# ZHSD-ZYNQ-PWR.net
KiCad netlist of a schematic drawn in Altium Designer
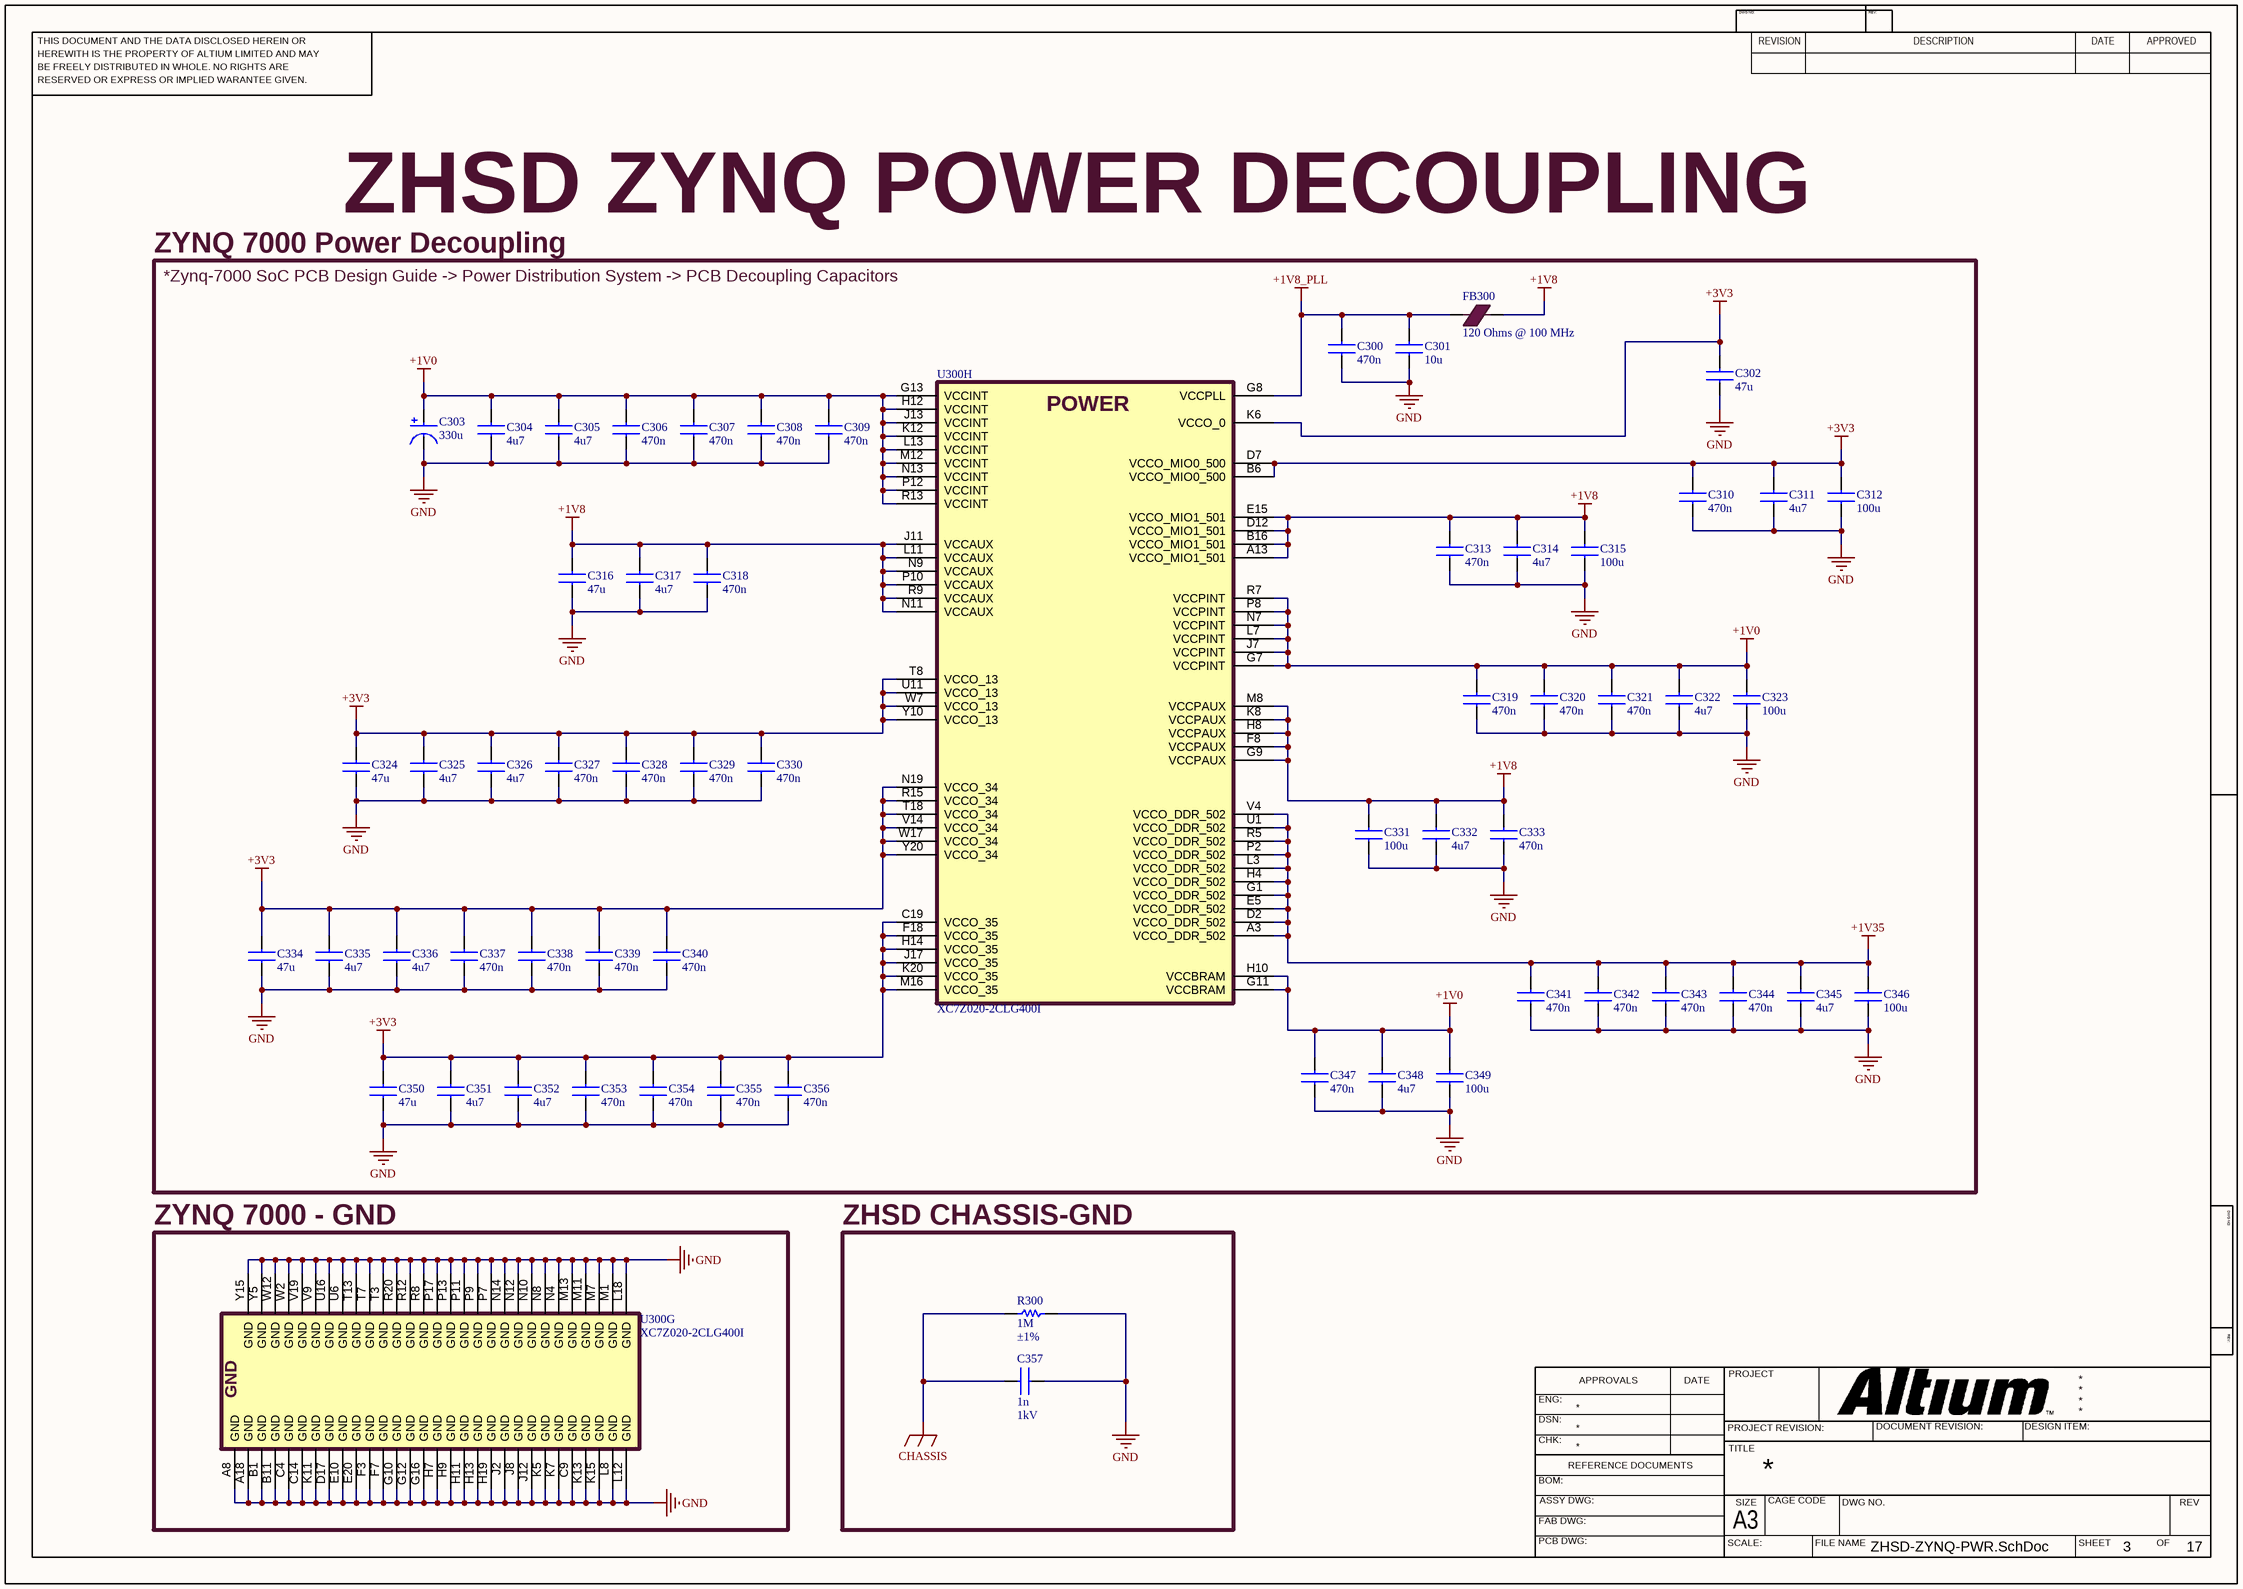
[diagram p0: ZHSD-ZYNQ-PWR.SchDoc]

(export (version "E")
  (design (tool "Eeschema 10.0.6"))
  (components
    (comp (ref "C300")
      (value "470n")
      (footprint "0402CAPC1005X06N")
      (description "CAP CER 0.47UF 6.3V X5R 0402(1005) ±10%")
      (fields (field (name "MANUFACTURER") "Murata Electronics") (field (name "MPN") "GRM155R60J474KE19D"))
      (libsource (lib "UK_Library") (part "GRM155R60J474KE19D"))
    )
    (comp (ref "C301")
      (value "10u")
      (footprint "0603CAPC1608X09N")
      (description "CAP CER 10UF 4V X5R 0603 (1608) ±20%")
      (fields (field (name "MANUFACTURER") "Murata Electronics") (field (name "MPN") "GRM188R60G106ME47D"))
      (libsource (lib "UK_Library") (part "GRM188R60G106ME47D"))
    )
    (comp (ref "C302")
      (value "47u")
      (footprint "1210CAPC3225X27N")
      (description "CAP CER 47UF 6.3V X7R 1210 1210 (3225) ±20%")
      (fields (field (name "MANUFACTURER") "Murata Electronics") (field (name "MPN") "GRM32ER70J476ME20L"))
      (libsource (lib "UK_Library") (part "GRM32ER70J476ME20L"))
    )
    (comp (ref "C303")
      (value "330u")
      (footprint "T525D337M006ATE025")
      (description "CAP TANT POLY 330UF 6.3V 2917 (7343) ±20%")
      (fields (field (name "MANUFACTURER") "KEMET") (field (name "MPN") "T525D337M006ATE025"))
      (libsource (lib "UK_Library") (part "T525D337M006ATE025"))
    )
    (comp (ref "C304")
      (value "4u7")
      (footprint "0603CAPC1608X09N")
      (description "CAP CER 4.7UF 10V X5R 0603 (1608) ±10%")
      (fields
        (field (name "MANUFACTURER") "Samsung Electro-Mechanics")
        (field (name "MPN") "CL10A475KP8NNNC")
      )
      (libsource (lib "UK_Library") (part "CL10A475KP8NNNC"))
    )
    (comp (ref "C305")
      (value "4u7")
      (footprint "0603CAPC1608X09N")
      (description "CAP CER 4.7UF 10V X5R 0603 (1608) ±10%")
      (fields
        (field (name "MANUFACTURER") "Samsung Electro-Mechanics")
        (field (name "MPN") "CL10A475KP8NNNC")
      )
      (libsource (lib "UK_Library") (part "CL10A475KP8NNNC"))
    )
    (comp (ref "C306")
      (value "470n")
      (footprint "0402CAPC1005X06N")
      (description "CAP CER 0.47UF 6.3V X5R 0402(1005) ±10%")
      (fields (field (name "MANUFACTURER") "Murata Electronics") (field (name "MPN") "GRM155R60J474KE19D"))
      (libsource (lib "UK_Library") (part "GRM155R60J474KE19D"))
    )
    (comp (ref "C307")
      (value "470n")
      (footprint "0402CAPC1005X06N")
      (description "CAP CER 0.47UF 6.3V X5R 0402(1005) ±10%")
      (fields (field (name "MANUFACTURER") "Murata Electronics") (field (name "MPN") "GRM155R60J474KE19D"))
      (libsource (lib "UK_Library") (part "GRM155R60J474KE19D"))
    )
    (comp (ref "C308")
      (value "470n")
      (footprint "0402CAPC1005X06N")
      (description "CAP CER 0.47UF 6.3V X5R 0402(1005) ±10%")
      (fields (field (name "MANUFACTURER") "Murata Electronics") (field (name "MPN") "GRM155R60J474KE19D"))
      (libsource (lib "UK_Library") (part "GRM155R60J474KE19D"))
    )
    (comp (ref "C309")
      (value "470n")
      (footprint "0402CAPC1005X06N")
      (description "CAP CER 0.47UF 6.3V X5R 0402(1005) ±10%")
      (fields (field (name "MANUFACTURER") "Murata Electronics") (field (name "MPN") "GRM155R60J474KE19D"))
      (libsource (lib "UK_Library") (part "GRM155R60J474KE19D"))
    )
    (comp (ref "C310")
      (value "470n")
      (footprint "0402CAPC1005X06N")
      (description "CAP CER 0.47UF 6.3V X5R 0402(1005) ±10%")
      (fields (field (name "MANUFACTURER") "Murata Electronics") (field (name "MPN") "GRM155R60J474KE19D"))
      (libsource (lib "UK_Library") (part "GRM155R60J474KE19D"))
    )
    (comp (ref "C311")
      (value "4u7")
      (footprint "0603CAPC1608X09N")
      (description "CAP CER 4.7UF 10V X5R 0603 (1608) ±10%")
      (fields
        (field (name "MANUFACTURER") "Samsung Electro-Mechanics")
        (field (name "MPN") "CL10A475KP8NNNC")
      )
      (libsource (lib "UK_Library") (part "CL10A475KP8NNNC"))
    )
    (comp (ref "C312")
      (value "100u")
      (footprint "1210CAPC3225X27N")
      (description "CAP CER 100UF 4V X7U 1210 (3225) ±20%")
      (fields (field (name "MANUFACTURER") "Murata Electronics") (field (name "MPN") "GRM32EE70G107ME19L"))
      (libsource (lib "UK_Library") (part "GRM32EE70G107ME19L"))
    )
    (comp (ref "C313")
      (value "470n")
      (footprint "0402CAPC1005X06N")
      (description "CAP CER 0.47UF 6.3V X5R 0402(1005) ±10%")
      (fields (field (name "MANUFACTURER") "Murata Electronics") (field (name "MPN") "GRM155R60J474KE19D"))
      (libsource (lib "UK_Library") (part "GRM155R60J474KE19D"))
    )
    (comp (ref "C314")
      (value "4u7")
      (footprint "0603CAPC1608X09N")
      (description "CAP CER 4.7UF 10V X5R 0603 (1608) ±10%")
      (fields
        (field (name "MANUFACTURER") "Samsung Electro-Mechanics")
        (field (name "MPN") "CL10A475KP8NNNC")
      )
      (libsource (lib "UK_Library") (part "CL10A475KP8NNNC"))
    )
    (comp (ref "C315")
      (value "100u")
      (footprint "1210CAPC3225X27N")
      (description "CAP CER 100UF 4V X7U 1210 (3225) ±20%")
      (fields (field (name "MANUFACTURER") "Murata Electronics") (field (name "MPN") "GRM32EE70G107ME19L"))
      (libsource (lib "UK_Library") (part "GRM32EE70G107ME19L"))
    )
    (comp (ref "C316")
      (value "47u")
      (footprint "1210CAPC3225X27N")
      (description "CAP CER 47UF 6.3V X7R 1210 1210 (3225) ±20%")
      (fields (field (name "MANUFACTURER") "Murata Electronics") (field (name "MPN") "GRM32ER70J476ME20L"))
      (libsource (lib "UK_Library") (part "GRM32ER70J476ME20L"))
    )
    (comp (ref "C317")
      (value "4u7")
      (footprint "0603CAPC1608X09N")
      (description "CAP CER 4.7UF 10V X5R 0603 (1608) ±10%")
      (fields
        (field (name "MANUFACTURER") "Samsung Electro-Mechanics")
        (field (name "MPN") "CL10A475KP8NNNC")
      )
      (libsource (lib "UK_Library") (part "CL10A475KP8NNNC"))
    )
    (comp (ref "C318")
      (value "470n")
      (footprint "0402CAPC1005X06N")
      (description "CAP CER 0.47UF 6.3V X5R 0402(1005) ±10%")
      (fields (field (name "MANUFACTURER") "Murata Electronics") (field (name "MPN") "GRM155R60J474KE19D"))
      (libsource (lib "UK_Library") (part "GRM155R60J474KE19D"))
    )
    (comp (ref "C319")
      (value "470n")
      (footprint "0402CAPC1005X06N")
      (description "CAP CER 0.47UF 6.3V X5R 0402(1005) ±10%")
      (fields (field (name "MANUFACTURER") "Murata Electronics") (field (name "MPN") "GRM155R60J474KE19D"))
      (libsource (lib "UK_Library") (part "GRM155R60J474KE19D"))
    )
    (comp (ref "C320")
      (value "470n")
      (footprint "0402CAPC1005X06N")
      (description "CAP CER 0.47UF 6.3V X5R 0402(1005) ±10%")
      (fields (field (name "MANUFACTURER") "Murata Electronics") (field (name "MPN") "GRM155R60J474KE19D"))
      (libsource (lib "UK_Library") (part "GRM155R60J474KE19D"))
    )
    (comp (ref "C321")
      (value "470n")
      (footprint "0402CAPC1005X06N")
      (description "CAP CER 0.47UF 6.3V X5R 0402(1005) ±10%")
      (fields (field (name "MANUFACTURER") "Murata Electronics") (field (name "MPN") "GRM155R60J474KE19D"))
      (libsource (lib "UK_Library") (part "GRM155R60J474KE19D"))
    )
    (comp (ref "C322")
      (value "4u7")
      (footprint "0603CAPC1608X09N")
      (description "CAP CER 4.7UF 10V X5R 0603 (1608) ±10%")
      (fields
        (field (name "MANUFACTURER") "Samsung Electro-Mechanics")
        (field (name "MPN") "CL10A475KP8NNNC")
      )
      (libsource (lib "UK_Library") (part "CL10A475KP8NNNC"))
    )
    (comp (ref "C323")
      (value "100u")
      (footprint "1210CAPC3225X27N")
      (description "CAP CER 100UF 4V X7U 1210 (3225) ±20%")
      (fields (field (name "MANUFACTURER") "Murata Electronics") (field (name "MPN") "GRM32EE70G107ME19L"))
      (libsource (lib "UK_Library") (part "GRM32EE70G107ME19L"))
    )
    (comp (ref "C324")
      (value "47u")
      (footprint "1210CAPC3225X27N")
      (description "CAP CER 47UF 6.3V X7R 1210 1210 (3225) ±20%")
      (fields (field (name "MANUFACTURER") "Murata Electronics") (field (name "MPN") "GRM32ER70J476ME20L"))
      (libsource (lib "UK_Library") (part "GRM32ER70J476ME20L"))
    )
    (comp (ref "C325")
      (value "4u7")
      (footprint "0603CAPC1608X09N")
      (description "CAP CER 4.7UF 10V X5R 0603 (1608) ±10%")
      (fields
        (field (name "MANUFACTURER") "Samsung Electro-Mechanics")
        (field (name "MPN") "CL10A475KP8NNNC")
      )
      (libsource (lib "UK_Library") (part "CL10A475KP8NNNC"))
    )
    (comp (ref "C326")
      (value "4u7")
      (footprint "0603CAPC1608X09N")
      (description "CAP CER 4.7UF 10V X5R 0603 (1608) ±10%")
      (fields
        (field (name "MANUFACTURER") "Samsung Electro-Mechanics")
        (field (name "MPN") "CL10A475KP8NNNC")
      )
      (libsource (lib "UK_Library") (part "CL10A475KP8NNNC"))
    )
    (comp (ref "C327")
      (value "470n")
      (footprint "0402CAPC1005X06N")
      (description "CAP CER 0.47UF 6.3V X5R 0402(1005) ±10%")
      (fields (field (name "MANUFACTURER") "Murata Electronics") (field (name "MPN") "GRM155R60J474KE19D"))
      (libsource (lib "UK_Library") (part "GRM155R60J474KE19D"))
    )
    (comp (ref "C328")
      (value "470n")
      (footprint "0402CAPC1005X06N")
      (description "CAP CER 0.47UF 6.3V X5R 0402(1005) ±10%")
      (fields (field (name "MANUFACTURER") "Murata Electronics") (field (name "MPN") "GRM155R60J474KE19D"))
      (libsource (lib "UK_Library") (part "GRM155R60J474KE19D"))
    )
    (comp (ref "C329")
      (value "470n")
      (footprint "0402CAPC1005X06N")
      (description "CAP CER 0.47UF 6.3V X5R 0402(1005) ±10%")
      (fields (field (name "MANUFACTURER") "Murata Electronics") (field (name "MPN") "GRM155R60J474KE19D"))
      (libsource (lib "UK_Library") (part "GRM155R60J474KE19D"))
    )
    (comp (ref "C330")
      (value "470n")
      (footprint "0402CAPC1005X06N")
      (description "CAP CER 0.47UF 6.3V X5R 0402(1005) ±10%")
      (fields (field (name "MANUFACTURER") "Murata Electronics") (field (name "MPN") "GRM155R60J474KE19D"))
      (libsource (lib "UK_Library") (part "GRM155R60J474KE19D"))
    )
    (comp (ref "C331")
      (value "100u")
      (footprint "1210CAPC3225X27N")
      (description "CAP CER 100UF 4V X7U 1210 (3225) ±20%")
      (fields (field (name "MANUFACTURER") "Murata Electronics") (field (name "MPN") "GRM32EE70G107ME19L"))
      (libsource (lib "UK_Library") (part "GRM32EE70G107ME19L"))
    )
    (comp (ref "C332")
      (value "4u7")
      (footprint "0603CAPC1608X09N")
      (description "CAP CER 4.7UF 10V X5R 0603 (1608) ±10%")
      (fields
        (field (name "MANUFACTURER") "Samsung Electro-Mechanics")
        (field (name "MPN") "CL10A475KP8NNNC")
      )
      (libsource (lib "UK_Library") (part "CL10A475KP8NNNC"))
    )
    (comp (ref "C333")
      (value "470n")
      (footprint "0402CAPC1005X06N")
      (description "CAP CER 0.47UF 6.3V X5R 0402(1005) ±10%")
      (fields (field (name "MANUFACTURER") "Murata Electronics") (field (name "MPN") "GRM155R60J474KE19D"))
      (libsource (lib "UK_Library") (part "GRM155R60J474KE19D"))
    )
    (comp (ref "C334")
      (value "47u")
      (footprint "1210CAPC3225X27N")
      (description "CAP CER 47UF 6.3V X7R 1210 1210 (3225) ±20%")
      (fields (field (name "MANUFACTURER") "Murata Electronics") (field (name "MPN") "GRM32ER70J476ME20L"))
      (libsource (lib "UK_Library") (part "GRM32ER70J476ME20L"))
    )
    (comp (ref "C335")
      (value "4u7")
      (footprint "0603CAPC1608X09N")
      (description "CAP CER 4.7UF 10V X5R 0603 (1608) ±10%")
      (fields
        (field (name "MANUFACTURER") "Samsung Electro-Mechanics")
        (field (name "MPN") "CL10A475KP8NNNC")
      )
      (libsource (lib "UK_Library") (part "CL10A475KP8NNNC"))
    )
    (comp (ref "C336")
      (value "4u7")
      (footprint "0603CAPC1608X09N")
      (description "CAP CER 4.7UF 10V X5R 0603 (1608) ±10%")
      (fields
        (field (name "MANUFACTURER") "Samsung Electro-Mechanics")
        (field (name "MPN") "CL10A475KP8NNNC")
      )
      (libsource (lib "UK_Library") (part "CL10A475KP8NNNC"))
    )
    (comp (ref "C337")
      (value "470n")
      (footprint "0402CAPC1005X06N")
      (description "CAP CER 0.47UF 6.3V X5R 0402(1005) ±10%")
      (fields (field (name "MANUFACTURER") "Murata Electronics") (field (name "MPN") "GRM155R60J474KE19D"))
      (libsource (lib "UK_Library") (part "GRM155R60J474KE19D"))
    )
    (comp (ref "C338")
      (value "470n")
      (footprint "0402CAPC1005X06N")
      (description "CAP CER 0.47UF 6.3V X5R 0402(1005) ±10%")
      (fields (field (name "MANUFACTURER") "Murata Electronics") (field (name "MPN") "GRM155R60J474KE19D"))
      (libsource (lib "UK_Library") (part "GRM155R60J474KE19D"))
    )
    (comp (ref "C339")
      (value "470n")
      (footprint "0402CAPC1005X06N")
      (description "CAP CER 0.47UF 6.3V X5R 0402(1005) ±10%")
      (fields (field (name "MANUFACTURER") "Murata Electronics") (field (name "MPN") "GRM155R60J474KE19D"))
      (libsource (lib "UK_Library") (part "GRM155R60J474KE19D"))
    )
    (comp (ref "C340")
      (value "470n")
      (footprint "0402CAPC1005X06N")
      (description "CAP CER 0.47UF 6.3V X5R 0402(1005) ±10%")
      (fields (field (name "MANUFACTURER") "Murata Electronics") (field (name "MPN") "GRM155R60J474KE19D"))
      (libsource (lib "UK_Library") (part "GRM155R60J474KE19D"))
    )
    (comp (ref "C341")
      (value "470n")
      (footprint "0402CAPC1005X06N")
      (description "CAP CER 0.47UF 6.3V X5R 0402(1005) ±10%")
      (fields (field (name "MANUFACTURER") "Murata Electronics") (field (name "MPN") "GRM155R60J474KE19D"))
      (libsource (lib "UK_Library") (part "GRM155R60J474KE19D"))
    )
    (comp (ref "C342")
      (value "470n")
      (footprint "0402CAPC1005X06N")
      (description "CAP CER 0.47UF 6.3V X5R 0402(1005) ±10%")
      (fields (field (name "MANUFACTURER") "Murata Electronics") (field (name "MPN") "GRM155R60J474KE19D"))
      (libsource (lib "UK_Library") (part "GRM155R60J474KE19D"))
    )
    (comp (ref "C343")
      (value "470n")
      (footprint "0402CAPC1005X06N")
      (description "CAP CER 0.47UF 6.3V X5R 0402(1005) ±10%")
      (fields (field (name "MANUFACTURER") "Murata Electronics") (field (name "MPN") "GRM155R60J474KE19D"))
      (libsource (lib "UK_Library") (part "GRM155R60J474KE19D"))
    )
    (comp (ref "C344")
      (value "470n")
      (footprint "0402CAPC1005X06N")
      (description "CAP CER 0.47UF 6.3V X5R 0402(1005) ±10%")
      (fields (field (name "MANUFACTURER") "Murata Electronics") (field (name "MPN") "GRM155R60J474KE19D"))
      (libsource (lib "UK_Library") (part "GRM155R60J474KE19D"))
    )
    (comp (ref "C345")
      (value "4u7")
      (footprint "0603CAPC1608X09N")
      (description "CAP CER 4.7UF 10V X5R 0603 (1608) ±10%")
      (fields
        (field (name "MANUFACTURER") "Samsung Electro-Mechanics")
        (field (name "MPN") "CL10A475KP8NNNC")
      )
      (libsource (lib "UK_Library") (part "CL10A475KP8NNNC"))
    )
    (comp (ref "C346")
      (value "100u")
      (footprint "1210CAPC3225X27N")
      (description "CAP CER 100UF 4V X7U 1210 (3225) ±20%")
      (fields (field (name "MANUFACTURER") "Murata Electronics") (field (name "MPN") "GRM32EE70G107ME19L"))
      (libsource (lib "UK_Library") (part "GRM32EE70G107ME19L"))
    )
    (comp (ref "C347")
      (value "470n")
      (footprint "0402CAPC1005X06N")
      (description "CAP CER 0.47UF 6.3V X5R 0402(1005) ±10%")
      (fields (field (name "MANUFACTURER") "Murata Electronics") (field (name "MPN") "GRM155R60J474KE19D"))
      (libsource (lib "UK_Library") (part "GRM155R60J474KE19D"))
    )
    (comp (ref "C348")
      (value "4u7")
      (footprint "0603CAPC1608X09N")
      (description "CAP CER 4.7UF 10V X5R 0603 (1608) ±10%")
      (fields
        (field (name "MANUFACTURER") "Samsung Electro-Mechanics")
        (field (name "MPN") "CL10A475KP8NNNC")
      )
      (libsource (lib "UK_Library") (part "CL10A475KP8NNNC"))
    )
    (comp (ref "C349")
      (value "100u")
      (footprint "1210CAPC3225X27N")
      (description "CAP CER 100UF 4V X7U 1210 (3225) ±20%")
      (fields (field (name "MANUFACTURER") "Murata Electronics") (field (name "MPN") "GRM32EE70G107ME19L"))
      (libsource (lib "UK_Library") (part "GRM32EE70G107ME19L"))
    )
    (comp (ref "C350")
      (value "47u")
      (footprint "1210CAPC3225X27N")
      (description "CAP CER 47UF 6.3V X7R 1210 1210 (3225) ±20%")
      (fields (field (name "MANUFACTURER") "Murata Electronics") (field (name "MPN") "GRM32ER70J476ME20L"))
      (libsource (lib "UK_Library") (part "GRM32ER70J476ME20L"))
    )
    (comp (ref "C351")
      (value "4u7")
      (footprint "0603CAPC1608X09N")
      (description "CAP CER 4.7UF 10V X5R 0603 (1608) ±10%")
      (fields
        (field (name "MANUFACTURER") "Samsung Electro-Mechanics")
        (field (name "MPN") "CL10A475KP8NNNC")
      )
      (libsource (lib "UK_Library") (part "CL10A475KP8NNNC"))
    )
    (comp (ref "C352")
      (value "4u7")
      (footprint "0603CAPC1608X09N")
      (description "CAP CER 4.7UF 10V X5R 0603 (1608) ±10%")
      (fields
        (field (name "MANUFACTURER") "Samsung Electro-Mechanics")
        (field (name "MPN") "CL10A475KP8NNNC")
      )
      (libsource (lib "UK_Library") (part "CL10A475KP8NNNC"))
    )
    (comp (ref "C353")
      (value "470n")
      (footprint "0402CAPC1005X06N")
      (description "CAP CER 0.47UF 6.3V X5R 0402(1005) ±10%")
      (fields (field (name "MANUFACTURER") "Murata Electronics") (field (name "MPN") "GRM155R60J474KE19D"))
      (libsource (lib "UK_Library") (part "GRM155R60J474KE19D"))
    )
    (comp (ref "C354")
      (value "470n")
      (footprint "0402CAPC1005X06N")
      (description "CAP CER 0.47UF 6.3V X5R 0402(1005) ±10%")
      (fields (field (name "MANUFACTURER") "Murata Electronics") (field (name "MPN") "GRM155R60J474KE19D"))
      (libsource (lib "UK_Library") (part "GRM155R60J474KE19D"))
    )
    (comp (ref "C355")
      (value "470n")
      (footprint "0402CAPC1005X06N")
      (description "CAP CER 0.47UF 6.3V X5R 0402(1005) ±10%")
      (fields (field (name "MANUFACTURER") "Murata Electronics") (field (name "MPN") "GRM155R60J474KE19D"))
      (libsource (lib "UK_Library") (part "GRM155R60J474KE19D"))
    )
    (comp (ref "C356")
      (value "470n")
      (footprint "0402CAPC1005X06N")
      (description "CAP CER 0.47UF 6.3V X5R 0402(1005) ±10%")
      (fields (field (name "MANUFACTURER") "Murata Electronics") (field (name "MPN") "GRM155R60J474KE19D"))
      (libsource (lib "UK_Library") (part "GRM155R60J474KE19D"))
    )
    (comp (ref "C357")
      (value "1n")
      (footprint "0805CAPC2012X14N")
      (description "CAP CER 1000PF 1KV X7R 0805 (2012) ±10%")
      (fields
        (field (name "MANUFACTURER") "YAGEO")
        (field (name "MPN") "CC0805KRX7RCBB102")
        (field (name "VOLTAGE") "1kV")
      )
      (libsource (lib "UK_Library") (part "CC0805KRX7RCBB102"))
    )
    (comp (ref "FB300")
      (value "120 Ohms @ 100 MHz")
      (footprint "0603INDC1608X08N")
      (description "FERRITE BEAD 120 OHM 0603 (1608) 3A 25mOhm")
      (fields (field (name "MANUFACTURER") "Murata Electronics") (field (name "MPN") "BLM18SG121TN1D"))
      (libsource (lib "UK_Library") (part "BLM18SG121TN1D"))
    )
    (comp (ref "R300")
      (value "1M")
      (footprint "0603RESC1608X05N")
      (description "RES SMD 1M OHM 1% 1/8W 0603 (1608)")
      (fields
        (field (name "MANUFACTURER") "Vishay Dale")
        (field (name "MPN") "CRCW06031M00FKEA")
        (field (name "TOLERANCE") "±1%")
      )
      (libsource (lib "UK_Library") (part "CRCW06031M00FKEA"))
    )
    (comp (ref "U300")
      (value "XC7Z020-2CLG400I")
      (footprint "BGA400C80P20X20_1700X1700X147")
      (fields (field (name "MANUFACTURER") "AMD/XILINX"))
      (libsource (lib "") (part "XC7Z020-2CLG400I_1"))
    )
  )
  (nets
    (net (code "1") (name "+1V0") (class "Default")
      (node (ref "C303") (pin "1") (pinfunction "1_1") (pintype "passive"))
      (node (ref "C304") (pin "2") (pinfunction "2_2") (pintype "passive"))
      (node (ref "C305") (pin "2") (pinfunction "2_2") (pintype "passive"))
      (node (ref "C306") (pin "2") (pinfunction "2_2") (pintype "passive"))
      (node (ref "C307") (pin "2") (pinfunction "2_2") (pintype "passive"))
      (node (ref "C308") (pin "2") (pinfunction "2_2") (pintype "passive"))
      (node (ref "C309") (pin "2") (pinfunction "2_2") (pintype "passive"))
      (node (ref "C319") (pin "2") (pinfunction "2_2") (pintype "passive"))
      (node (ref "C320") (pin "2") (pinfunction "2_2") (pintype "passive"))
      (node (ref "C321") (pin "2") (pinfunction "2_2") (pintype "passive"))
      (node (ref "C322") (pin "2") (pinfunction "2_2") (pintype "passive"))
      (node (ref "C323") (pin "1") (pinfunction "1_1") (pintype "passive"))
      (node (ref "C347") (pin "2") (pinfunction "2_2") (pintype "passive"))
      (node (ref "C348") (pin "2") (pinfunction "2_2") (pintype "passive"))
      (node (ref "C349") (pin "1") (pinfunction "1_1") (pintype "passive"))
      (node (ref "U300") (pin "G11") (pinfunction "VCCBRAM_G11") (pintype "power_in"))
      (node (ref "U300") (pin "G13") (pinfunction "VCCINT_G13") (pintype "power_in"))
      (node (ref "U300") (pin "G7") (pinfunction "VCCPINT_G7") (pintype "power_in"))
      (node (ref "U300") (pin "H10") (pinfunction "VCCBRAM_H10") (pintype "power_in"))
      (node (ref "U300") (pin "H12") (pinfunction "VCCINT_H12") (pintype "power_in"))
      (node (ref "U300") (pin "J13") (pinfunction "VCCINT_J13") (pintype "power_in"))
      (node (ref "U300") (pin "J7") (pinfunction "VCCPINT_J7") (pintype "power_in"))
      (node (ref "U300") (pin "K12") (pinfunction "VCCINT_K12") (pintype "power_in"))
      (node (ref "U300") (pin "L13") (pinfunction "VCCINT_L13") (pintype "power_in"))
      (node (ref "U300") (pin "L7") (pinfunction "VCCPINT_L7") (pintype "power_in"))
      (node (ref "U300") (pin "M12") (pinfunction "VCCINT_M12") (pintype "power_in"))
      (node (ref "U300") (pin "N13") (pinfunction "VCCINT_N13") (pintype "power_in"))
      (node (ref "U300") (pin "N7") (pinfunction "VCCPINT_N7") (pintype "power_in"))
      (node (ref "U300") (pin "P12") (pinfunction "VCCINT_P12") (pintype "power_in"))
      (node (ref "U300") (pin "P8") (pinfunction "VCCPINT_P8") (pintype "power_in"))
      (node (ref "U300") (pin "R13") (pinfunction "VCCINT_R13") (pintype "power_in"))
      (node (ref "U300") (pin "R7") (pinfunction "VCCPINT_R7") (pintype "power_in"))
    )
    (net (code "2") (name "+1V8") (class "Default")
      (node (ref "C313") (pin "2") (pinfunction "2_2") (pintype "passive"))
      (node (ref "C314") (pin "2") (pinfunction "2_2") (pintype "passive"))
      (node (ref "C315") (pin "1") (pinfunction "1_1") (pintype "passive"))
      (node (ref "C316") (pin "2") (pinfunction "2_2") (pintype "passive"))
      (node (ref "C317") (pin "2") (pinfunction "2_2") (pintype "passive"))
      (node (ref "C318") (pin "2") (pinfunction "2_2") (pintype "passive"))
      (node (ref "C331") (pin "1") (pinfunction "1_1") (pintype "passive"))
      (node (ref "C332") (pin "2") (pinfunction "2_2") (pintype "passive"))
      (node (ref "C333") (pin "2") (pinfunction "2_2") (pintype "passive"))
      (node (ref "FB300") (pin "2") (pinfunction "2_2") (pintype "passive"))
      (node (ref "U300") (pin "A13") (pinfunction "VCCO_MIO1_501_A13") (pintype "power_in"))
      (node (ref "U300") (pin "B16") (pinfunction "VCCO_MIO1_501_B16") (pintype "power_in"))
      (node (ref "U300") (pin "D12") (pinfunction "VCCO_MIO1_501_D12") (pintype "power_in"))
      (node (ref "U300") (pin "E15") (pinfunction "VCCO_MIO1_501_E15") (pintype "power_in"))
      (node (ref "U300") (pin "F8") (pinfunction "VCCPAUX_F8") (pintype "power_in"))
      (node (ref "U300") (pin "G9") (pinfunction "VCCPAUX_G9") (pintype "power_in"))
      (node (ref "U300") (pin "H8") (pinfunction "VCCPAUX_H8") (pintype "power_in"))
      (node (ref "U300") (pin "J11") (pinfunction "VCCAUX_J11") (pintype "power_in"))
      (node (ref "U300") (pin "K8") (pinfunction "VCCPAUX_K8") (pintype "power_in"))
      (node (ref "U300") (pin "L11") (pinfunction "VCCAUX_L11") (pintype "power_in"))
      (node (ref "U300") (pin "M8") (pinfunction "VCCPAUX_M8") (pintype "power_in"))
      (node (ref "U300") (pin "N11") (pinfunction "VCCAUX_N11") (pintype "power_in"))
      (node (ref "U300") (pin "N9") (pinfunction "VCCAUX_N9") (pintype "power_in"))
      (node (ref "U300") (pin "P10") (pinfunction "VCCAUX_P10") (pintype "power_in"))
      (node (ref "U300") (pin "R9") (pinfunction "VCCAUX_R9") (pintype "power_in"))
    )
    (net (code "3") (name "+1V8_PLL") (class "Default")
      (node (ref "C300") (pin "2") (pinfunction "2_2") (pintype "passive"))
      (node (ref "C301") (pin "2") (pinfunction "2_2") (pintype "passive"))
      (node (ref "FB300") (pin "1") (pinfunction "1_1") (pintype "passive"))
      (node (ref "U300") (pin "G8") (pinfunction "VCCPLL_G8") (pintype "power_in"))
    )
    (net (code "4") (name "+1V35") (class "Default")
      (node (ref "C341") (pin "2") (pinfunction "2_2") (pintype "passive"))
      (node (ref "C342") (pin "2") (pinfunction "2_2") (pintype "passive"))
      (node (ref "C343") (pin "2") (pinfunction "2_2") (pintype "passive"))
      (node (ref "C344") (pin "2") (pinfunction "2_2") (pintype "passive"))
      (node (ref "C345") (pin "2") (pinfunction "2_2") (pintype "passive"))
      (node (ref "C346") (pin "1") (pinfunction "1_1") (pintype "passive"))
      (node (ref "U300") (pin "A3") (pinfunction "VCCO_DDR_502_A3") (pintype "power_in"))
      (node (ref "U300") (pin "D2") (pinfunction "VCCO_DDR_502_D2") (pintype "power_in"))
      (node (ref "U300") (pin "E5") (pinfunction "VCCO_DDR_502_E5") (pintype "power_in"))
      (node (ref "U300") (pin "G1") (pinfunction "VCCO_DDR_502_G1") (pintype "power_in"))
      (node (ref "U300") (pin "H4") (pinfunction "VCCO_DDR_502_H4") (pintype "power_in"))
      (node (ref "U300") (pin "L3") (pinfunction "VCCO_DDR_502_L3") (pintype "power_in"))
      (node (ref "U300") (pin "P2") (pinfunction "VCCO_DDR_502_P2") (pintype "power_in"))
      (node (ref "U300") (pin "R5") (pinfunction "VCCO_DDR_502_R5") (pintype "power_in"))
      (node (ref "U300") (pin "U1") (pinfunction "VCCO_DDR_502_U1") (pintype "power_in"))
      (node (ref "U300") (pin "V4") (pinfunction "VCCO_DDR_502_V4") (pintype "power_in"))
    )
    (net (code "5") (name "+3V3") (class "Default")
      (node (ref "C302") (pin "2") (pinfunction "2_2") (pintype "passive"))
      (node (ref "C310") (pin "2") (pinfunction "2_2") (pintype "passive"))
      (node (ref "C311") (pin "2") (pinfunction "2_2") (pintype "passive"))
      (node (ref "C312") (pin "1") (pinfunction "1_1") (pintype "passive"))
      (node (ref "C324") (pin "2") (pinfunction "2_2") (pintype "passive"))
      (node (ref "C325") (pin "2") (pinfunction "2_2") (pintype "passive"))
      (node (ref "C326") (pin "2") (pinfunction "2_2") (pintype "passive"))
      (node (ref "C327") (pin "2") (pinfunction "2_2") (pintype "passive"))
      (node (ref "C328") (pin "2") (pinfunction "2_2") (pintype "passive"))
      (node (ref "C329") (pin "2") (pinfunction "2_2") (pintype "passive"))
      (node (ref "C330") (pin "2") (pinfunction "2_2") (pintype "passive"))
      (node (ref "C334") (pin "2") (pinfunction "2_2") (pintype "passive"))
      (node (ref "C335") (pin "2") (pinfunction "2_2") (pintype "passive"))
      (node (ref "C336") (pin "2") (pinfunction "2_2") (pintype "passive"))
      (node (ref "C337") (pin "2") (pinfunction "2_2") (pintype "passive"))
      (node (ref "C338") (pin "2") (pinfunction "2_2") (pintype "passive"))
      (node (ref "C339") (pin "2") (pinfunction "2_2") (pintype "passive"))
      (node (ref "C340") (pin "2") (pinfunction "2_2") (pintype "passive"))
      (node (ref "C350") (pin "2") (pinfunction "2_2") (pintype "passive"))
      (node (ref "C351") (pin "2") (pinfunction "2_2") (pintype "passive"))
      (node (ref "C352") (pin "2") (pinfunction "2_2") (pintype "passive"))
      (node (ref "C353") (pin "2") (pinfunction "2_2") (pintype "passive"))
      (node (ref "C354") (pin "2") (pinfunction "2_2") (pintype "passive"))
      (node (ref "C355") (pin "2") (pinfunction "2_2") (pintype "passive"))
      (node (ref "C356") (pin "2") (pinfunction "2_2") (pintype "passive"))
      (node (ref "U300") (pin "B6") (pinfunction "VCCO_MIO0_500_B6") (pintype "power_in"))
      (node (ref "U300") (pin "C19") (pinfunction "VCCO_35_C19") (pintype "power_in"))
      (node (ref "U300") (pin "D7") (pinfunction "VCCO_MIO0_500_D7") (pintype "power_in"))
      (node (ref "U300") (pin "F18") (pinfunction "VCCO_35_F18") (pintype "power_in"))
      (node (ref "U300") (pin "H14") (pinfunction "VCCO_35_H14") (pintype "power_in"))
      (node (ref "U300") (pin "J17") (pinfunction "VCCO_35_J17") (pintype "power_in"))
      (node (ref "U300") (pin "K20") (pinfunction "VCCO_35_K20") (pintype "power_in"))
      (node (ref "U300") (pin "K6") (pinfunction "VCCO_0_K6") (pintype "power_in"))
      (node (ref "U300") (pin "M16") (pinfunction "VCCO_35_M16") (pintype "power_in"))
      (node (ref "U300") (pin "N19") (pinfunction "VCCO_34_N19") (pintype "power_in"))
      (node (ref "U300") (pin "R15") (pinfunction "VCCO_34_R15") (pintype "power_in"))
      (node (ref "U300") (pin "T18") (pinfunction "VCCO_34_T18") (pintype "power_in"))
      (node (ref "U300") (pin "T8") (pinfunction "VCCO_13_T8") (pintype "power_in"))
      (node (ref "U300") (pin "U11") (pinfunction "VCCO_13_U11") (pintype "power_in"))
      (node (ref "U300") (pin "V14") (pinfunction "VCCO_34_V14") (pintype "power_in"))
      (node (ref "U300") (pin "W17") (pinfunction "VCCO_34_W17") (pintype "power_in"))
      (node (ref "U300") (pin "W7") (pinfunction "VCCO_13_W7") (pintype "power_in"))
      (node (ref "U300") (pin "Y10") (pinfunction "VCCO_13_Y10") (pintype "power_in"))
      (node (ref "U300") (pin "Y20") (pinfunction "VCCO_34_Y20") (pintype "power_in"))
    )
    (net (code "6") (name "CHASSIS") (class "Default")
      (node (ref "C357") (pin "2") (pinfunction "2_2") (pintype "passive"))
      (node (ref "R300") (pin "1") (pinfunction "1_1") (pintype "passive"))
    )
    (net (code "7") (name "GND") (class "Default")
      (node (ref "C300") (pin "1") (pinfunction "1_1") (pintype "passive"))
      (node (ref "C301") (pin "1") (pinfunction "1_1") (pintype "passive"))
      (node (ref "C302") (pin "1") (pinfunction "1_1") (pintype "passive"))
      (node (ref "C303") (pin "2") (pinfunction "2_2") (pintype "passive"))
      (node (ref "C304") (pin "1") (pinfunction "1_1") (pintype "passive"))
      (node (ref "C305") (pin "1") (pinfunction "1_1") (pintype "passive"))
      (node (ref "C306") (pin "1") (pinfunction "1_1") (pintype "passive"))
      (node (ref "C307") (pin "1") (pinfunction "1_1") (pintype "passive"))
      (node (ref "C308") (pin "1") (pinfunction "1_1") (pintype "passive"))
      (node (ref "C309") (pin "1") (pinfunction "1_1") (pintype "passive"))
      (node (ref "C310") (pin "1") (pinfunction "1_1") (pintype "passive"))
      (node (ref "C311") (pin "1") (pinfunction "1_1") (pintype "passive"))
      (node (ref "C312") (pin "2") (pinfunction "2_2") (pintype "passive"))
      (node (ref "C313") (pin "1") (pinfunction "1_1") (pintype "passive"))
      (node (ref "C314") (pin "1") (pinfunction "1_1") (pintype "passive"))
      (node (ref "C315") (pin "2") (pinfunction "2_2") (pintype "passive"))
      (node (ref "C316") (pin "1") (pinfunction "1_1") (pintype "passive"))
      (node (ref "C317") (pin "1") (pinfunction "1_1") (pintype "passive"))
      (node (ref "C318") (pin "1") (pinfunction "1_1") (pintype "passive"))
      (node (ref "C319") (pin "1") (pinfunction "1_1") (pintype "passive"))
      (node (ref "C320") (pin "1") (pinfunction "1_1") (pintype "passive"))
      (node (ref "C321") (pin "1") (pinfunction "1_1") (pintype "passive"))
      (node (ref "C322") (pin "1") (pinfunction "1_1") (pintype "passive"))
      (node (ref "C323") (pin "2") (pinfunction "2_2") (pintype "passive"))
      (node (ref "C324") (pin "1") (pinfunction "1_1") (pintype "passive"))
      (node (ref "C325") (pin "1") (pinfunction "1_1") (pintype "passive"))
      (node (ref "C326") (pin "1") (pinfunction "1_1") (pintype "passive"))
      (node (ref "C327") (pin "1") (pinfunction "1_1") (pintype "passive"))
      (node (ref "C328") (pin "1") (pinfunction "1_1") (pintype "passive"))
      (node (ref "C329") (pin "1") (pinfunction "1_1") (pintype "passive"))
      (node (ref "C330") (pin "1") (pinfunction "1_1") (pintype "passive"))
      (node (ref "C331") (pin "2") (pinfunction "2_2") (pintype "passive"))
      (node (ref "C332") (pin "1") (pinfunction "1_1") (pintype "passive"))
      (node (ref "C333") (pin "1") (pinfunction "1_1") (pintype "passive"))
      (node (ref "C334") (pin "1") (pinfunction "1_1") (pintype "passive"))
      (node (ref "C335") (pin "1") (pinfunction "1_1") (pintype "passive"))
      (node (ref "C336") (pin "1") (pinfunction "1_1") (pintype "passive"))
      (node (ref "C337") (pin "1") (pinfunction "1_1") (pintype "passive"))
      (node (ref "C338") (pin "1") (pinfunction "1_1") (pintype "passive"))
      (node (ref "C339") (pin "1") (pinfunction "1_1") (pintype "passive"))
      (node (ref "C340") (pin "1") (pinfunction "1_1") (pintype "passive"))
      (node (ref "C341") (pin "1") (pinfunction "1_1") (pintype "passive"))
      (node (ref "C342") (pin "1") (pinfunction "1_1") (pintype "passive"))
      (node (ref "C343") (pin "1") (pinfunction "1_1") (pintype "passive"))
      (node (ref "C344") (pin "1") (pinfunction "1_1") (pintype "passive"))
      (node (ref "C345") (pin "1") (pinfunction "1_1") (pintype "passive"))
      (node (ref "C346") (pin "2") (pinfunction "2_2") (pintype "passive"))
      (node (ref "C347") (pin "1") (pinfunction "1_1") (pintype "passive"))
      (node (ref "C348") (pin "1") (pinfunction "1_1") (pintype "passive"))
      (node (ref "C349") (pin "2") (pinfunction "2_2") (pintype "passive"))
      (node (ref "C350") (pin "1") (pinfunction "1_1") (pintype "passive"))
      (node (ref "C351") (pin "1") (pinfunction "1_1") (pintype "passive"))
      (node (ref "C352") (pin "1") (pinfunction "1_1") (pintype "passive"))
      (node (ref "C353") (pin "1") (pinfunction "1_1") (pintype "passive"))
      (node (ref "C354") (pin "1") (pinfunction "1_1") (pintype "passive"))
      (node (ref "C355") (pin "1") (pinfunction "1_1") (pintype "passive"))
      (node (ref "C356") (pin "1") (pinfunction "1_1") (pintype "passive"))
      (node (ref "C357") (pin "1") (pinfunction "1_1") (pintype "passive"))
      (node (ref "R300") (pin "2") (pinfunction "2_2") (pintype "passive"))
      (node (ref "U300") (pin "A18") (pinfunction "GND_A18") (pintype "power_in"))
      (node (ref "U300") (pin "A8") (pinfunction "GND_A8") (pintype "power_in"))
      (node (ref "U300") (pin "B1") (pinfunction "GND_B1") (pintype "power_in"))
      (node (ref "U300") (pin "B11") (pinfunction "GND_B11") (pintype "power_in"))
      (node (ref "U300") (pin "C14") (pinfunction "GND_C14") (pintype "power_in"))
      (node (ref "U300") (pin "C4") (pinfunction "GND_C4") (pintype "power_in"))
      (node (ref "U300") (pin "C9") (pinfunction "GND_C9") (pintype "power_in"))
      (node (ref "U300") (pin "D17") (pinfunction "GND_D17") (pintype "power_in"))
      (node (ref "U300") (pin "E10") (pinfunction "GND_E10") (pintype "power_in"))
      (node (ref "U300") (pin "E20") (pinfunction "GND_E20") (pintype "power_in"))
      (node (ref "U300") (pin "F3") (pinfunction "GND_F3") (pintype "power_in"))
      (node (ref "U300") (pin "F7") (pinfunction "GND_F7") (pintype "power_in"))
      (node (ref "U300") (pin "G10") (pinfunction "GND_G10") (pintype "power_in"))
      (node (ref "U300") (pin "G12") (pinfunction "GND_G12") (pintype "power_in"))
      (node (ref "U300") (pin "G16") (pinfunction "GND_G16") (pintype "power_in"))
      (node (ref "U300") (pin "H11") (pinfunction "GND_H11") (pintype "power_in"))
      (node (ref "U300") (pin "H13") (pinfunction "GND_H13") (pintype "power_in"))
      (node (ref "U300") (pin "H19") (pinfunction "GND_H19") (pintype "power_in"))
      (node (ref "U300") (pin "H7") (pinfunction "GND_H7") (pintype "power_in"))
      (node (ref "U300") (pin "H9") (pinfunction "GND_H9") (pintype "power_in"))
      (node (ref "U300") (pin "J12") (pinfunction "GND_J12") (pintype "power_in"))
      (node (ref "U300") (pin "J2") (pinfunction "GND_J2") (pintype "power_in"))
      (node (ref "U300") (pin "J8") (pinfunction "GND_J8") (pintype "power_in"))
      (node (ref "U300") (pin "K11") (pinfunction "GND_K11") (pintype "power_in"))
      (node (ref "U300") (pin "K13") (pinfunction "GND_K13") (pintype "power_in"))
      (node (ref "U300") (pin "K15") (pinfunction "GND_K15") (pintype "power_in"))
      (node (ref "U300") (pin "K5") (pinfunction "GND_K5") (pintype "power_in"))
      (node (ref "U300") (pin "K7") (pinfunction "GND_K7") (pintype "power_in"))
      (node (ref "U300") (pin "L12") (pinfunction "GND_L12") (pintype "power_in"))
      (node (ref "U300") (pin "L18") (pinfunction "GND_L18") (pintype "power_in"))
      (node (ref "U300") (pin "L8") (pinfunction "GND_L8") (pintype "power_in"))
      (node (ref "U300") (pin "M1") (pinfunction "GND_M1") (pintype "power_in"))
      (node (ref "U300") (pin "M11") (pinfunction "GND_M11") (pintype "power_in"))
      (node (ref "U300") (pin "M13") (pinfunction "GND_M13") (pintype "power_in"))
      (node (ref "U300") (pin "M7") (pinfunction "GND_M7") (pintype "power_in"))
      (node (ref "U300") (pin "N10") (pinfunction "GND_N10") (pintype "power_in"))
      (node (ref "U300") (pin "N12") (pinfunction "GND_N12") (pintype "power_in"))
      (node (ref "U300") (pin "N14") (pinfunction "GND_N14") (pintype "power_in"))
      (node (ref "U300") (pin "N4") (pinfunction "GND_N4") (pintype "power_in"))
      (node (ref "U300") (pin "N8") (pinfunction "GND_N8") (pintype "power_in"))
      (node (ref "U300") (pin "P11") (pinfunction "GND_P11") (pintype "power_in"))
      (node (ref "U300") (pin "P13") (pinfunction "GND_P13") (pintype "power_in"))
      (node (ref "U300") (pin "P17") (pinfunction "GND_P17") (pintype "power_in"))
      (node (ref "U300") (pin "P7") (pinfunction "GND_P7") (pintype "power_in"))
      (node (ref "U300") (pin "P9") (pinfunction "GND_P9") (pintype "power_in"))
      (node (ref "U300") (pin "R12") (pinfunction "GND_R12") (pintype "power_in"))
      (node (ref "U300") (pin "R20") (pinfunction "GND_R20") (pintype "power_in"))
      (node (ref "U300") (pin "R8") (pinfunction "GND_R8") (pintype "power_in"))
      (node (ref "U300") (pin "T13") (pinfunction "GND_T13") (pintype "power_in"))
      (node (ref "U300") (pin "T3") (pinfunction "GND_T3") (pintype "power_in"))
      (node (ref "U300") (pin "T7") (pinfunction "GND_T7") (pintype "power_in"))
      (node (ref "U300") (pin "U16") (pinfunction "GND_U16") (pintype "power_in"))
      (node (ref "U300") (pin "U6") (pinfunction "GND_U6") (pintype "power_in"))
      (node (ref "U300") (pin "V19") (pinfunction "GND_V19") (pintype "power_in"))
      (node (ref "U300") (pin "V9") (pinfunction "GND_V9") (pintype "power_in"))
      (node (ref "U300") (pin "W12") (pinfunction "GND_W12") (pintype "power_in"))
      (node (ref "U300") (pin "W2") (pinfunction "GND_W2") (pintype "power_in"))
      (node (ref "U300") (pin "Y15") (pinfunction "GND_Y15") (pintype "power_in"))
      (node (ref "U300") (pin "Y5") (pinfunction "GND_Y5") (pintype "power_in"))
    )
  )
)
